# 11_-_CONNECTOR.net
KiCad netlist of a schematic drawn in Altium Designer
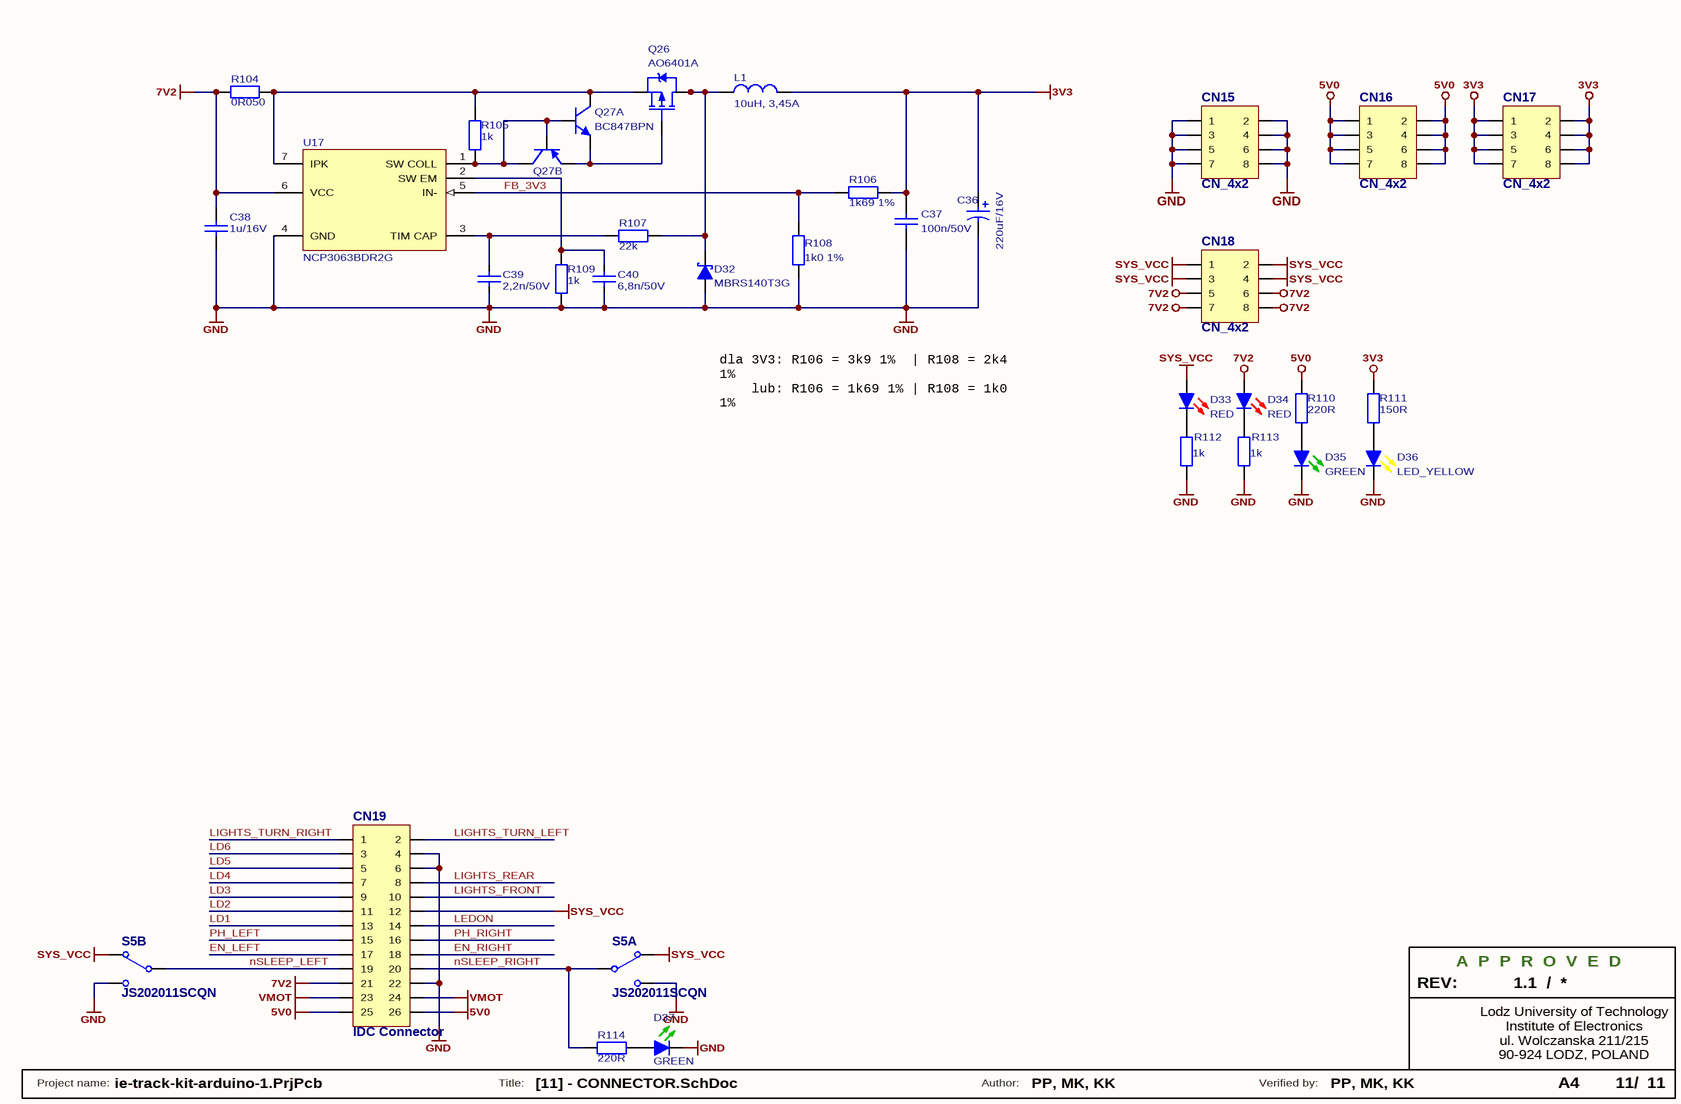
[diagram p0: [11] - CONNECTOR.SchDoc]

(export (version "E")
  (design (tool "Eeschema 10.0.6"))
  (components
    (comp (ref "C36")
      (value "220uF/16V")
      (footprint "CES_E_8.3x8.3_6.2")
      (description "Polarized Capacitor")
      (libsource (lib "capacitors") (part "Cap Pol"))
    )
    (comp (ref "C37")
      (value "100n/50V")
      (footprint "C0805")
      (description "Capacitor")
      (libsource (lib "") (part "Cap_1"))
    )
    (comp (ref "C38")
      (value "1u/16V")
      (footprint "C0805")
      (description "Capacitor")
      (libsource (lib "") (part "Cap_2"))
    )
    (comp (ref "C39")
      (value "2,2n/50V")
      (footprint "C0805")
      (description "Capacitor")
      (libsource (lib "capacitors") (part "Cap"))
    )
    (comp (ref "C40")
      (value "6,8n/50V")
      (footprint "C0805")
      (description "Capacitor")
      (libsource (lib "capacitors") (part "Cap"))
    )
    (comp (ref "CN15") (value "CN_4x2") (footprint "GP_4x2") (libsource (lib "goldpin_male") (part "CN_4x2")))
    (comp (ref "CN16") (value "CN_4x2") (footprint "GP_4x2") (libsource (lib "goldpin_male") (part "CN_4x2")))
    (comp (ref "CN17") (value "CN_4x2") (footprint "GP_4x2") (libsource (lib "goldpin_male") (part "CN_4x2")))
    (comp (ref "CN18") (value "CN_4x2") (footprint "GP_4x2") (libsource (lib "goldpin_male") (part "CN_4x2")))
    (comp (ref "CN19")
      (value "IDC Connector")
      (footprint "IDC26_RA_LONG_W_CN")
      (libsource (lib "idc") (part "CN_13x2"))
    )
    (comp (ref "D32")
      (value "MBRS140T3G")
      (footprint "SMB")
      (description "Schottky barrier rectifier: 40V, 1A")
      (libsource (lib "diodes_schottky") (part "MBRS140T3G"))
    )
    (comp (ref "D33")
      (value "RED")
      (footprint "LED0805R")
      (description "RED LED")
      (libsource (lib "leds") (part "LED_RED"))
    )
    (comp (ref "D34")
      (value "RED")
      (footprint "LED0805R")
      (description "RED LED")
      (libsource (lib "leds") (part "LED_RED"))
    )
    (comp (ref "D35")
      (value "GREEN")
      (footprint "LED0805G")
      (description "GREEN LED")
      (libsource (lib "leds") (part "LED_GREEN"))
    )
    (comp (ref "D36")
      (value "LED_YELLOW")
      (footprint "LED0805Y")
      (description "YELLOW LED")
      (libsource (lib "leds") (part "LED_YELLOW"))
    )
    (comp (ref "D37")
      (value "GREEN")
      (footprint "LED0805G")
      (description "GREEN LED")
      (libsource (lib "leds") (part "LED_GREEN"))
    )
    (comp (ref "L1")
      (value "10uH, 3,45A")
      (footprint "PSDB1005")
      (description "10uH, 20%, 3,45A, PSDB1005N Series Inductor")
      (libsource (lib "inductors") (part "PSDB1005NT100"))
    )
    (comp (ref "Q26")
      (value "AO6401A")
      (footprint "SOT-23-6")
      (description "P-Channel MOSFET; -60V, -5A, 1.3W;")
      (libsource (lib "transistors_mos") (part "AO6401A"))
    )
    (comp (ref "Q27")
      (value "BC847BPN")
      (footprint "SOT-323-6 (SOT-363, SC88, SC70-6)")
      (description "PNP/NPN General Purpose Transistor (VCE=45V, IC=100mA)")
      (libsource (lib "transistors_bjt") (part "BC847BPN"))
    )
    (comp (ref "R104")
      (value "0R050")
      (footprint "R0805")
      (description "Resistor")
      (libsource (lib "") (part "Res_1"))
    )
    (comp (ref "R105")
      (value "1k")
      (footprint "R0805")
      (description "Resistor")
      (libsource (lib "resistors") (part "Res"))
    )
    (comp (ref "R106")
      (value "1k69 1%")
      (footprint "R0805")
      (description "Resistor")
      (libsource (lib "") (part "Res_1"))
    )
    (comp (ref "R107")
      (value "22k")
      (footprint "R0805")
      (description "Resistor")
      (libsource (lib "") (part "Res_2"))
    )
    (comp (ref "R108")
      (value "1k0 1%")
      (footprint "R0805")
      (description "Resistor")
      (libsource (lib "resistors") (part "Res"))
    )
    (comp (ref "R109")
      (value "1k")
      (footprint "R0805")
      (description "Resistor")
      (libsource (lib "resistors") (part "Res"))
    )
    (comp (ref "R110")
      (value "220R")
      (footprint "R0805")
      (description "Resistor")
      (libsource (lib "resistors") (part "Res"))
    )
    (comp (ref "R111")
      (value "150R")
      (footprint "R0805")
      (description "Resistor")
      (libsource (lib "resistors") (part "Res"))
    )
    (comp (ref "R112")
      (value "1k")
      (footprint "R0805")
      (description "Resistor")
      (libsource (lib "resistors") (part "Res"))
    )
    (comp (ref "R113")
      (value "1k")
      (footprint "R0805")
      (description "Resistor")
      (libsource (lib "resistors") (part "Res"))
    )
    (comp (ref "R114")
      (value "220R")
      (footprint "R0805")
      (description "Resistor")
      (libsource (lib "") (part "Res_1"))
    )
    (comp (ref "S5")
      (value "JS202011SCQN")
      (footprint "JS202011SCQN")
      (description "C&K JS202011SCQN DPDT Switch")
      (fields (field (name "PUBLISHER") "Altium Limited"))
      (libsource (lib "") (part "JS202011SCQN_1"))
    )
    (comp (ref "U17")
      (value "NCP3063BDR2G")
      (footprint "SO8")
      (description "DC-DC Converter NCP3063BDR2G (Farnell 1547126)")
      (libsource (lib "switched_voltage_regulators") (part "NCP3063BDR2G"))
    )
  )
  (nets
    (net (code "1") (name "/EN_LEFT") (class "Default")
      (node (ref "CN19") (pin "17") (pinfunction "17_17") (pintype "passive"))
    )
    (net (code "2") (name "/EN_RIGHT") (class "Default")
      (node (ref "CN19") (pin "18") (pinfunction "18_18") (pintype "passive"))
    )
    (net (code "3") (name "/FB_3V3") (class "Default")
      (node (ref "R106") (pin "1") (pinfunction "1_1") (pintype "passive"))
      (node (ref "R108") (pin "1") (pinfunction "1_1") (pintype "passive"))
      (node (ref "U17") (pin "5") (pinfunction "IN-_5") (pintype "input"))
    )
    (net (code "4") (name "/LD1") (class "Default")
      (node (ref "CN19") (pin "13") (pinfunction "13_13") (pintype "passive"))
    )
    (net (code "5") (name "/LD2") (class "Default")
      (node (ref "CN19") (pin "11") (pinfunction "11_11") (pintype "passive"))
    )
    (net (code "6") (name "/LD3") (class "Default")
      (node (ref "CN19") (pin "9") (pinfunction "9_9") (pintype "passive"))
    )
    (net (code "7") (name "/LD4") (class "Default")
      (node (ref "CN19") (pin "7") (pinfunction "7_7") (pintype "passive"))
    )
    (net (code "8") (name "/LD5") (class "Default")
      (node (ref "CN19") (pin "5") (pinfunction "5_5") (pintype "passive"))
    )
    (net (code "9") (name "/LD6") (class "Default")
      (node (ref "CN19") (pin "3") (pinfunction "3_3") (pintype "passive"))
    )
    (net (code "10") (name "/LEDON") (class "Default")
      (node (ref "CN19") (pin "14") (pinfunction "14_14") (pintype "passive"))
    )
    (net (code "11") (name "/LIGHTS_FRONT") (class "Default")
      (node (ref "CN19") (pin "10") (pinfunction "10_10") (pintype "passive"))
    )
    (net (code "12") (name "/LIGHTS_REAR") (class "Default")
      (node (ref "CN19") (pin "8") (pinfunction "8_8") (pintype "passive"))
    )
    (net (code "13") (name "/LIGHTS_TURN_LEFT") (class "Default")
      (node (ref "CN19") (pin "2") (pinfunction "2_2") (pintype "passive"))
    )
    (net (code "14") (name "/LIGHTS_TURN_RIGHT") (class "Default")
      (node (ref "CN19") (pin "1") (pinfunction "1_1") (pintype "passive"))
    )
    (net (code "15") (name "/PH_LEFT") (class "Default")
      (node (ref "CN19") (pin "15") (pinfunction "15_15") (pintype "passive"))
    )
    (net (code "16") (name "/PH_RIGHT") (class "Default")
      (node (ref "CN19") (pin "16") (pinfunction "16_16") (pintype "passive"))
    )
    (net (code "17") (name "/nSLEEP_LEFT") (class "Default")
      (node (ref "CN19") (pin "19") (pinfunction "19_19") (pintype "passive"))
      (node (ref "S5") (pin "5") (pinfunction "COMMON2_5") (pintype "passive"))
    )
    (net (code "18") (name "/nSLEEP_RIGHT") (class "Default")
      (node (ref "CN19") (pin "20") (pinfunction "20_20") (pintype "passive"))
      (node (ref "R114") (pin "1") (pinfunction "1_1") (pintype "passive"))
      (node (ref "S5") (pin "1") (pinfunction "COMMON1_1") (pintype "passive"))
    )
    (net (code "19") (name "3V3") (class "Default")
      (node (ref "C36") (pin "1") (pinfunction "1_1") (pintype "passive"))
      (node (ref "C37") (pin "2") (pinfunction "2_2") (pintype "passive"))
      (node (ref "CN17") (pin "1") (pinfunction "1_1") (pintype "passive"))
      (node (ref "CN17") (pin "2") (pinfunction "2_2") (pintype "passive"))
      (node (ref "CN17") (pin "3") (pinfunction "3_3") (pintype "passive"))
      (node (ref "CN17") (pin "4") (pinfunction "4_4") (pintype "passive"))
      (node (ref "CN17") (pin "5") (pinfunction "5_5") (pintype "passive"))
      (node (ref "CN17") (pin "6") (pinfunction "6_6") (pintype "passive"))
      (node (ref "CN17") (pin "7") (pinfunction "7_7") (pintype "passive"))
      (node (ref "CN17") (pin "8") (pinfunction "8_8") (pintype "passive"))
      (node (ref "L1") (pin "2") (pinfunction "2_2") (pintype "passive"))
      (node (ref "R106") (pin "2") (pinfunction "2_2") (pintype "passive"))
      (node (ref "R111") (pin "1") (pinfunction "1_1") (pintype "passive"))
    )
    (net (code "20") (name "5V0") (class "Default")
      (node (ref "CN16") (pin "1") (pinfunction "1_1") (pintype "passive"))
      (node (ref "CN16") (pin "2") (pinfunction "2_2") (pintype "passive"))
      (node (ref "CN16") (pin "3") (pinfunction "3_3") (pintype "passive"))
      (node (ref "CN16") (pin "4") (pinfunction "4_4") (pintype "passive"))
      (node (ref "CN16") (pin "5") (pinfunction "5_5") (pintype "passive"))
      (node (ref "CN16") (pin "6") (pinfunction "6_6") (pintype "passive"))
      (node (ref "CN16") (pin "7") (pinfunction "7_7") (pintype "passive"))
      (node (ref "CN16") (pin "8") (pinfunction "8_8") (pintype "passive"))
      (node (ref "CN19") (pin "25") (pinfunction "25_25") (pintype "passive"))
      (node (ref "CN19") (pin "26") (pinfunction "26_26") (pintype "passive"))
      (node (ref "R110") (pin "1") (pinfunction "1_1") (pintype "passive"))
    )
    (net (code "21") (name "7V2") (class "Default")
      (node (ref "C38") (pin "2") (pinfunction "2_2") (pintype "passive"))
      (node (ref "CN18") (pin "5") (pinfunction "5_5") (pintype "passive"))
      (node (ref "CN18") (pin "6") (pinfunction "6_6") (pintype "passive"))
      (node (ref "CN18") (pin "7") (pinfunction "7_7") (pintype "passive"))
      (node (ref "CN18") (pin "8") (pinfunction "8_8") (pintype "passive"))
      (node (ref "CN19") (pin "21") (pinfunction "21_21") (pintype "passive"))
      (node (ref "D34") (pin "1") (pinfunction "A_1") (pintype "passive"))
      (node (ref "R104") (pin "1") (pinfunction "1_1") (pintype "passive"))
      (node (ref "U17") (pin "6") (pinfunction "VCC_6") (pintype "power_in"))
    )
    (net (code "22") (name "GND") (class "Default")
      (node (ref "C36") (pin "2") (pinfunction "2_2") (pintype "passive"))
      (node (ref "C37") (pin "1") (pinfunction "1_1") (pintype "passive"))
      (node (ref "C38") (pin "1") (pinfunction "1_1") (pintype "passive"))
      (node (ref "C39") (pin "1") (pinfunction "1_1") (pintype "passive"))
      (node (ref "C40") (pin "1") (pinfunction "1_1") (pintype "passive"))
      (node (ref "CN15") (pin "1") (pinfunction "1_1") (pintype "passive"))
      (node (ref "CN15") (pin "2") (pinfunction "2_2") (pintype "passive"))
      (node (ref "CN15") (pin "3") (pinfunction "3_3") (pintype "passive"))
      (node (ref "CN15") (pin "4") (pinfunction "4_4") (pintype "passive"))
      (node (ref "CN15") (pin "5") (pinfunction "5_5") (pintype "passive"))
      (node (ref "CN15") (pin "6") (pinfunction "6_6") (pintype "passive"))
      (node (ref "CN15") (pin "7") (pinfunction "7_7") (pintype "passive"))
      (node (ref "CN15") (pin "8") (pinfunction "8_8") (pintype "passive"))
      (node (ref "CN19") (pin "22") (pinfunction "22_22") (pintype "passive"))
      (node (ref "CN19") (pin "4") (pinfunction "4_4") (pintype "passive"))
      (node (ref "CN19") (pin "6") (pinfunction "6_6") (pintype "passive"))
      (node (ref "D32") (pin "1") (pinfunction "A_1") (pintype "passive"))
      (node (ref "D35") (pin "2") (pinfunction "K_2") (pintype "passive"))
      (node (ref "D36") (pin "2") (pinfunction "K_2") (pintype "passive"))
      (node (ref "D37") (pin "2") (pinfunction "K_2") (pintype "passive"))
      (node (ref "R108") (pin "2") (pinfunction "2_2") (pintype "passive"))
      (node (ref "R109") (pin "2") (pinfunction "2_2") (pintype "passive"))
      (node (ref "R112") (pin "2") (pinfunction "2_2") (pintype "passive"))
      (node (ref "R113") (pin "2") (pinfunction "2_2") (pintype "passive"))
      (node (ref "S5") (pin "3") (pinfunction "NO1_3") (pintype "passive"))
      (node (ref "S5") (pin "6") (pinfunction "NO2_6") (pintype "passive"))
      (node (ref "U17") (pin "4") (pinfunction "GND_4") (pintype "power_in"))
    )
    (net (code "23") (name "Net-(D32-K)") (class "Default")
      (node (ref "D32") (pin "2") (pinfunction "K_2") (pintype "passive"))
      (node (ref "L1") (pin "1") (pinfunction "1_1") (pintype "passive"))
      (node (ref "Q26") (pin "1") (pinfunction "D_1") (pintype "passive"))
      (node (ref "Q26") (pin "2") (pinfunction "D_2") (pintype "passive"))
      (node (ref "Q26") (pin "5") (pinfunction "D_5") (pintype "passive"))
      (node (ref "Q26") (pin "6") (pinfunction "D_6") (pintype "passive"))
      (node (ref "R107") (pin "1") (pinfunction "1_1") (pintype "passive"))
    )
    (net (code "24") (name "Net-(D33-K)") (class "Default")
      (node (ref "D33") (pin "2") (pinfunction "K_2") (pintype "passive"))
      (node (ref "R112") (pin "1") (pinfunction "1_1") (pintype "passive"))
    )
    (net (code "25") (name "Net-(D34-K)") (class "Default")
      (node (ref "D34") (pin "2") (pinfunction "K_2") (pintype "passive"))
      (node (ref "R113") (pin "1") (pinfunction "1_1") (pintype "passive"))
    )
    (net (code "26") (name "Net-(D35-A)") (class "Default")
      (node (ref "D35") (pin "1") (pinfunction "A_1") (pintype "passive"))
      (node (ref "R110") (pin "2") (pinfunction "2_2") (pintype "passive"))
    )
    (net (code "27") (name "Net-(D36-A)") (class "Default")
      (node (ref "D36") (pin "1") (pinfunction "A_1") (pintype "passive"))
      (node (ref "R111") (pin "2") (pinfunction "2_2") (pintype "passive"))
    )
    (net (code "28") (name "Net-(D37-A)") (class "Default")
      (node (ref "D37") (pin "1") (pinfunction "A_1") (pintype "passive"))
      (node (ref "R114") (pin "2") (pinfunction "2_2") (pintype "passive"))
    )
    (net (code "29") (name "Net-(Q26-G)") (class "Default")
      (node (ref "Q26") (pin "3") (pinfunction "G_3") (pintype "passive"))
      (node (ref "Q27") (pin "1") (pinfunction "EA_1") (pintype "passive"))
      (node (ref "Q27") (pin "4") (pinfunction "EB_4") (pintype "passive"))
    )
    (net (code "30") (name "Net-(Q26-S)") (class "Default")
      (node (ref "Q26") (pin "4") (pinfunction "S_4") (pintype "passive"))
      (node (ref "Q27") (pin "6") (pinfunction "CA_6") (pintype "passive"))
      (node (ref "R104") (pin "2") (pinfunction "2_2") (pintype "passive"))
      (node (ref "R105") (pin "1") (pinfunction "1_1") (pintype "passive"))
      (node (ref "U17") (pin "7") (pinfunction "IPK_7") (pintype "passive"))
    )
    (net (code "31") (name "Net-(Q27A-BA)") (class "Default")
      (node (ref "Q27") (pin "2") (pinfunction "BA_2") (pintype "passive"))
      (node (ref "Q27") (pin "3") (pinfunction "CB_3") (pintype "passive"))
      (node (ref "Q27") (pin "5") (pinfunction "BB_5") (pintype "passive"))
      (node (ref "R105") (pin "2") (pinfunction "2_2") (pintype "passive"))
      (node (ref "U17") (pin "1") (pinfunction "SW_COLL_1") (pintype "passive"))
    )
    (net (code "32") (name "Net-(U17-SW_EM)") (class "Default")
      (node (ref "C40") (pin "2") (pinfunction "2_2") (pintype "passive"))
      (node (ref "R109") (pin "1") (pinfunction "1_1") (pintype "passive"))
      (node (ref "U17") (pin "2") (pinfunction "SW_EM_2") (pintype "passive"))
    )
    (net (code "33") (name "Net-(U17-TIM_CAP)") (class "Default")
      (node (ref "C39") (pin "2") (pinfunction "2_2") (pintype "passive"))
      (node (ref "R107") (pin "2") (pinfunction "2_2") (pintype "passive"))
      (node (ref "U17") (pin "3") (pinfunction "TIM_CAP_3") (pintype "passive"))
    )
    (net (code "34") (name "SYS_VCC") (class "Default")
      (node (ref "CN18") (pin "1") (pinfunction "1_1") (pintype "passive"))
      (node (ref "CN18") (pin "2") (pinfunction "2_2") (pintype "passive"))
      (node (ref "CN18") (pin "3") (pinfunction "3_3") (pintype "passive"))
      (node (ref "CN18") (pin "4") (pinfunction "4_4") (pintype "passive"))
      (node (ref "CN19") (pin "12") (pinfunction "12_12") (pintype "passive"))
      (node (ref "D33") (pin "1") (pinfunction "A_1") (pintype "passive"))
      (node (ref "S5") (pin "2") (pinfunction "NC1_2") (pintype "passive"))
      (node (ref "S5") (pin "4") (pinfunction "NC2_4") (pintype "passive"))
    )
    (net (code "35") (name "VMOT") (class "Default")
      (node (ref "CN19") (pin "23") (pinfunction "23_23") (pintype "passive"))
      (node (ref "CN19") (pin "24") (pinfunction "24_24") (pintype "passive"))
    )
  )
)
